# sparklecon2014_badge_v2.net
KiCad netlist of a schematic drawn in EAGLE
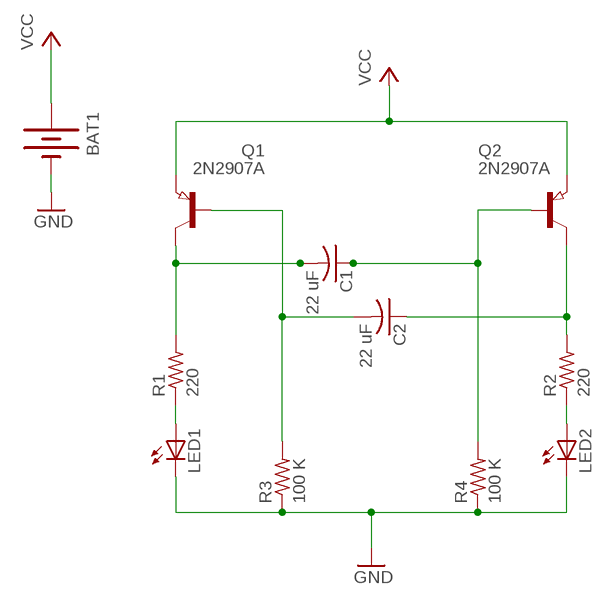
[diagram p0: schematic, sheet 1]
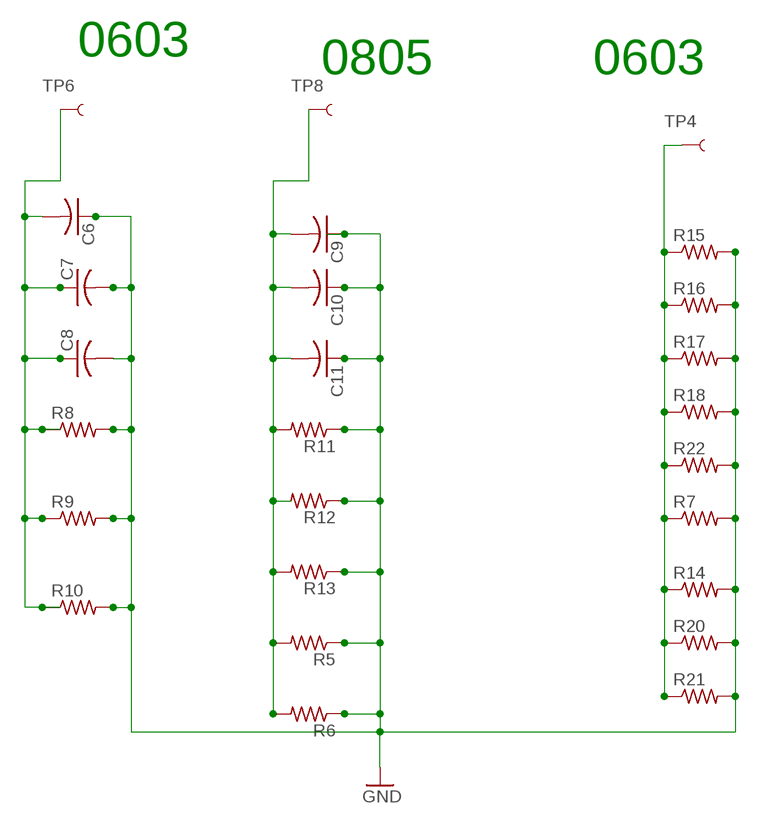
[diagram p1: schematic, sheet 2]

(export (version "E")
  (design (tool "Eeschema 10.0.6"))
  (components
    (comp (ref "BAT1")
      (value "BATTERY20PTH")
      (footprint "eagle-import:BATTCOM_20MM_PTH")
      (libsource (lib "eagle-import") (part "BATTERY20PTH"))
    )
    (comp (ref "C1")
      (value "22 uF")
      (footprint "eagle-import:C1206K")
      (libsource (lib "eagle-import") (part "resistor_C-USC1206K"))
    )
    (comp (ref "C2")
      (value "22 uF")
      (footprint "eagle-import:C1206K")
      (libsource (lib "eagle-import") (part "resistor_C-USC1206K"))
    )
    (comp (ref "LED1")
      (value "LEDCHIPLED_1206")
      (footprint "eagle-import:CHIPLED_1206")
      (libsource (lib "eagle-import") (part "LEDCHIPLED_1206"))
    )
    (comp (ref "LED2")
      (value "LEDCHIPLED_1206")
      (footprint "eagle-import:CHIPLED_1206")
      (libsource (lib "eagle-import") (part "LEDCHIPLED_1206"))
    )
    (comp (ref "Q1")
      (value "2N2907A")
      (footprint "eagle-import:SOT23")
      (libsource (lib "eagle-import") (part "PNP-TRANSISTOR_SOT23R"))
    )
    (comp (ref "Q2")
      (value "2N2907A")
      (footprint "eagle-import:SOT23")
      (libsource (lib "eagle-import") (part "PNP-TRANSISTOR_SOT23R"))
    )
    (comp (ref "R1")
      (value "220")
      (footprint "eagle-import:R0805")
      (libsource (lib "eagle-import") (part "R-US_R0805"))
    )
    (comp (ref "R2")
      (value "220")
      (footprint "eagle-import:R0805")
      (libsource (lib "eagle-import") (part "R-US_R0805"))
    )
    (comp (ref "R3")
      (value "100 K")
      (footprint "eagle-import:R0805")
      (libsource (lib "eagle-import") (part "R-US_R0805"))
    )
    (comp (ref "R4")
      (value "100 K")
      (footprint "eagle-import:R0805")
      (libsource (lib "eagle-import") (part "R-US_R0805"))
    )
    (comp (ref "C6")
      (value "C-USC1206")
      (footprint "eagle-import:C1206")
      (libsource (lib "eagle-import") (part "C-USC1206"))
    )
    (comp (ref "C7")
      (value "C-USC1206")
      (footprint "eagle-import:C1206")
      (libsource (lib "eagle-import") (part "C-USC1206"))
    )
    (comp (ref "C8")
      (value "C-USC1206")
      (footprint "eagle-import:C1206")
      (libsource (lib "eagle-import") (part "C-USC1206"))
    )
    (comp (ref "C9")
      (value "C-USC0805")
      (footprint "eagle-import:C0805")
      (libsource (lib "eagle-import") (part "C-USC0805"))
    )
    (comp (ref "C10")
      (value "C-USC0805")
      (footprint "eagle-import:C0805")
      (libsource (lib "eagle-import") (part "C-USC0805"))
    )
    (comp (ref "C11")
      (value "C-USC0805")
      (footprint "eagle-import:C0805")
      (libsource (lib "eagle-import") (part "C-USC0805"))
    )
    (comp (ref "R5")
      (value "R-US_R0805")
      (footprint "eagle-import:R0805")
      (libsource (lib "eagle-import") (part "R-US_R0805"))
    )
    (comp (ref "R6")
      (value "R-US_R0805")
      (footprint "eagle-import:R0805")
      (libsource (lib "eagle-import") (part "R-US_R0805"))
    )
    (comp (ref "R7")
      (value "R-US_R0402")
      (footprint "eagle-import:R0402")
      (libsource (lib "eagle-import") (part "resistor_R-US_R0402"))
    )
    (comp (ref "R8")
      (value "R-US_R1206")
      (footprint "eagle-import:R1206")
      (libsource (lib "eagle-import") (part "R-US_R1206"))
    )
    (comp (ref "R9")
      (value "R-US_R1206")
      (footprint "eagle-import:R1206")
      (libsource (lib "eagle-import") (part "R-US_R1206"))
    )
    (comp (ref "R10")
      (value "R-US_R1206")
      (footprint "eagle-import:R1206")
      (libsource (lib "eagle-import") (part "R-US_R1206"))
    )
    (comp (ref "R11")
      (value "R-US_R0805")
      (footprint "eagle-import:R0805")
      (libsource (lib "eagle-import") (part "R-US_R0805"))
    )
    (comp (ref "R12")
      (value "R-US_R0805")
      (footprint "eagle-import:R0805")
      (libsource (lib "eagle-import") (part "R-US_R0805"))
    )
    (comp (ref "R13")
      (value "R-US_R0805")
      (footprint "eagle-import:R0805")
      (libsource (lib "eagle-import") (part "R-US_R0805"))
    )
    (comp (ref "R14")
      (value "R-US_R0402")
      (footprint "eagle-import:R0402")
      (libsource (lib "eagle-import") (part "resistor_R-US_R0402"))
    )
    (comp (ref "R15")
      (value "R-US_R0603")
      (footprint "eagle-import:R0603")
      (libsource (lib "eagle-import") (part "resistor_R-US_R0603"))
    )
    (comp (ref "R16")
      (value "R-US_R0603")
      (footprint "eagle-import:R0603")
      (libsource (lib "eagle-import") (part "resistor_R-US_R0603"))
    )
    (comp (ref "R17")
      (value "R-US_R0603")
      (footprint "eagle-import:R0603")
      (libsource (lib "eagle-import") (part "resistor_R-US_R0603"))
    )
    (comp (ref "R18")
      (value "R-US_R0603")
      (footprint "eagle-import:R0603")
      (libsource (lib "eagle-import") (part "resistor_R-US_R0603"))
    )
    (comp (ref "R20")
      (value "R-US_R0402")
      (footprint "eagle-import:R0402")
      (libsource (lib "eagle-import") (part "resistor_R-US_R0402"))
    )
    (comp (ref "R21")
      (value "R-US_R0402")
      (footprint "eagle-import:R0402")
      (libsource (lib "eagle-import") (part "resistor_R-US_R0402"))
    )
    (comp (ref "R22")
      (value "R-US_R0402")
      (footprint "eagle-import:R0402")
      (libsource (lib "eagle-import") (part "resistor_R-US_R0402"))
    )
    (comp (ref "TP4")
      (value "TEST-POINT3X5")
      (footprint "eagle-import:PAD.03X.05")
      (libsource (lib "eagle-import") (part "TEST-POINT3X5"))
    )
    (comp (ref "TP6")
      (value "TEST-POINT3X5")
      (footprint "eagle-import:PAD.03X.05")
      (libsource (lib "eagle-import") (part "TEST-POINT3X5"))
    )
    (comp (ref "TP8")
      (value "TEST-POINT3X5")
      (footprint "eagle-import:PAD.03X.05")
      (libsource (lib "eagle-import") (part "TEST-POINT3X5"))
    )
  )
  (nets
    (net (code "1") (name "GND") (class "Default")
      (node (ref "BAT1") (pin "2") (pinfunction "-_2") (pintype "power_in"))
      (node (ref "C10") (pin "1") (pinfunction "1_1") (pintype "passive"))
      (node (ref "C11") (pin "1") (pinfunction "1_1") (pintype "passive"))
      (node (ref "C6") (pin "1") (pinfunction "1_1") (pintype "passive"))
      (node (ref "C7") (pin "2") (pinfunction "2_2") (pintype "passive"))
      (node (ref "C8") (pin "2") (pinfunction "2_2") (pintype "passive"))
      (node (ref "C9") (pin "1") (pinfunction "1_1") (pintype "passive"))
      (node (ref "LED1") (pin "C") (pinfunction "C_C") (pintype "passive"))
      (node (ref "LED2") (pin "C") (pinfunction "C_C") (pintype "passive"))
      (node (ref "R10") (pin "2") (pinfunction "2_2") (pintype "passive"))
      (node (ref "R11") (pin "1") (pinfunction "1_1") (pintype "passive"))
      (node (ref "R12") (pin "1") (pinfunction "1_1") (pintype "passive"))
      (node (ref "R13") (pin "1") (pinfunction "1_1") (pintype "passive"))
      (node (ref "R14") (pin "2") (pinfunction "2_2") (pintype "passive"))
      (node (ref "R15") (pin "2") (pinfunction "2_2") (pintype "passive"))
      (node (ref "R16") (pin "2") (pinfunction "2_2") (pintype "passive"))
      (node (ref "R17") (pin "2") (pinfunction "2_2") (pintype "passive"))
      (node (ref "R18") (pin "2") (pinfunction "2_2") (pintype "passive"))
      (node (ref "R20") (pin "2") (pinfunction "2_2") (pintype "passive"))
      (node (ref "R21") (pin "2") (pinfunction "2_2") (pintype "passive"))
      (node (ref "R22") (pin "2") (pinfunction "2_2") (pintype "passive"))
      (node (ref "R3") (pin "1") (pinfunction "1_1") (pintype "passive"))
      (node (ref "R4") (pin "1") (pinfunction "1_1") (pintype "passive"))
      (node (ref "R5") (pin "1") (pinfunction "1_1") (pintype "passive"))
      (node (ref "R6") (pin "1") (pinfunction "1_1") (pintype "passive"))
      (node (ref "R7") (pin "2") (pinfunction "2_2") (pintype "passive"))
      (node (ref "R8") (pin "2") (pinfunction "2_2") (pintype "passive"))
      (node (ref "R9") (pin "2") (pinfunction "2_2") (pintype "passive"))
    )
    (net (code "2") (name "Net-(LED1-PadA)") (class "Default")
      (node (ref "LED1") (pin "A") (pinfunction "A_A") (pintype "passive"))
      (node (ref "R1") (pin "1") (pinfunction "1_1") (pintype "passive"))
    )
    (net (code "3") (name "Net-(LED2-PadA)") (class "Default")
      (node (ref "LED2") (pin "A") (pinfunction "A_A") (pintype "passive"))
      (node (ref "R2") (pin "1") (pinfunction "1_1") (pintype "passive"))
    )
    (net (code "4") (name "Net-(Q1-B)") (class "Default")
      (node (ref "C2") (pin "2") (pinfunction "2_2") (pintype "passive"))
      (node (ref "Q1") (pin "1") (pinfunction "B_1") (pintype "passive"))
      (node (ref "R3") (pin "2") (pinfunction "2_2") (pintype "passive"))
    )
    (net (code "5") (name "Net-(Q1-C)") (class "Default")
      (node (ref "C1") (pin "2") (pinfunction "2_2") (pintype "passive"))
      (node (ref "Q1") (pin "3") (pinfunction "C_3") (pintype "passive"))
      (node (ref "R1") (pin "2") (pinfunction "2_2") (pintype "passive"))
    )
    (net (code "6") (name "Net-(Q2-B)") (class "Default")
      (node (ref "C1") (pin "1") (pinfunction "1_1") (pintype "passive"))
      (node (ref "Q2") (pin "1") (pinfunction "B_1") (pintype "passive"))
      (node (ref "R4") (pin "2") (pinfunction "2_2") (pintype "passive"))
    )
    (net (code "7") (name "Net-(Q2-C)") (class "Default")
      (node (ref "C2") (pin "1") (pinfunction "1_1") (pintype "passive"))
      (node (ref "Q2") (pin "3") (pinfunction "C_3") (pintype "passive"))
      (node (ref "R2") (pin "2") (pinfunction "2_2") (pintype "passive"))
    )
    (net (code "8") (name "Net-(TP4-1)") (class "Default")
      (node (ref "R14") (pin "1") (pinfunction "1_1") (pintype "passive"))
      (node (ref "R15") (pin "1") (pinfunction "1_1") (pintype "passive"))
      (node (ref "R16") (pin "1") (pinfunction "1_1") (pintype "passive"))
      (node (ref "R17") (pin "1") (pinfunction "1_1") (pintype "passive"))
      (node (ref "R18") (pin "1") (pinfunction "1_1") (pintype "passive"))
      (node (ref "R20") (pin "1") (pinfunction "1_1") (pintype "passive"))
      (node (ref "R21") (pin "1") (pinfunction "1_1") (pintype "passive"))
      (node (ref "R22") (pin "1") (pinfunction "1_1") (pintype "passive"))
      (node (ref "R7") (pin "1") (pinfunction "1_1") (pintype "passive"))
      (node (ref "TP4") (pin "P$1") (pinfunction "1_P$1") (pintype "bidirectional"))
    )
    (net (code "9") (name "Net-(TP6-1)") (class "Default")
      (node (ref "C6") (pin "2") (pinfunction "2_2") (pintype "passive"))
      (node (ref "C7") (pin "1") (pinfunction "1_1") (pintype "passive"))
      (node (ref "C8") (pin "1") (pinfunction "1_1") (pintype "passive"))
      (node (ref "R10") (pin "1") (pinfunction "1_1") (pintype "passive"))
      (node (ref "R8") (pin "1") (pinfunction "1_1") (pintype "passive"))
      (node (ref "R9") (pin "1") (pinfunction "1_1") (pintype "passive"))
      (node (ref "TP6") (pin "P$1") (pinfunction "1_P$1") (pintype "bidirectional"))
    )
    (net (code "10") (name "Net-(TP8-1)") (class "Default")
      (node (ref "C10") (pin "2") (pinfunction "2_2") (pintype "passive"))
      (node (ref "C11") (pin "2") (pinfunction "2_2") (pintype "passive"))
      (node (ref "C9") (pin "2") (pinfunction "2_2") (pintype "passive"))
      (node (ref "R11") (pin "2") (pinfunction "2_2") (pintype "passive"))
      (node (ref "R12") (pin "2") (pinfunction "2_2") (pintype "passive"))
      (node (ref "R13") (pin "2") (pinfunction "2_2") (pintype "passive"))
      (node (ref "R5") (pin "2") (pinfunction "2_2") (pintype "passive"))
      (node (ref "R6") (pin "2") (pinfunction "2_2") (pintype "passive"))
      (node (ref "TP8") (pin "P$1") (pinfunction "1_P$1") (pintype "bidirectional"))
    )
    (net (code "11") (name "VCC") (class "Default")
      (node (ref "BAT1") (pin "1") (pinfunction "+_1") (pintype "power_in"))
      (node (ref "Q1") (pin "2") (pinfunction "E_2") (pintype "passive"))
      (node (ref "Q2") (pin "2") (pinfunction "E_2") (pintype "passive"))
    )
  )
)
